# boatColorControlBiggerButtonV4.net
KiCad netlist of a schematic drawn in EAGLE
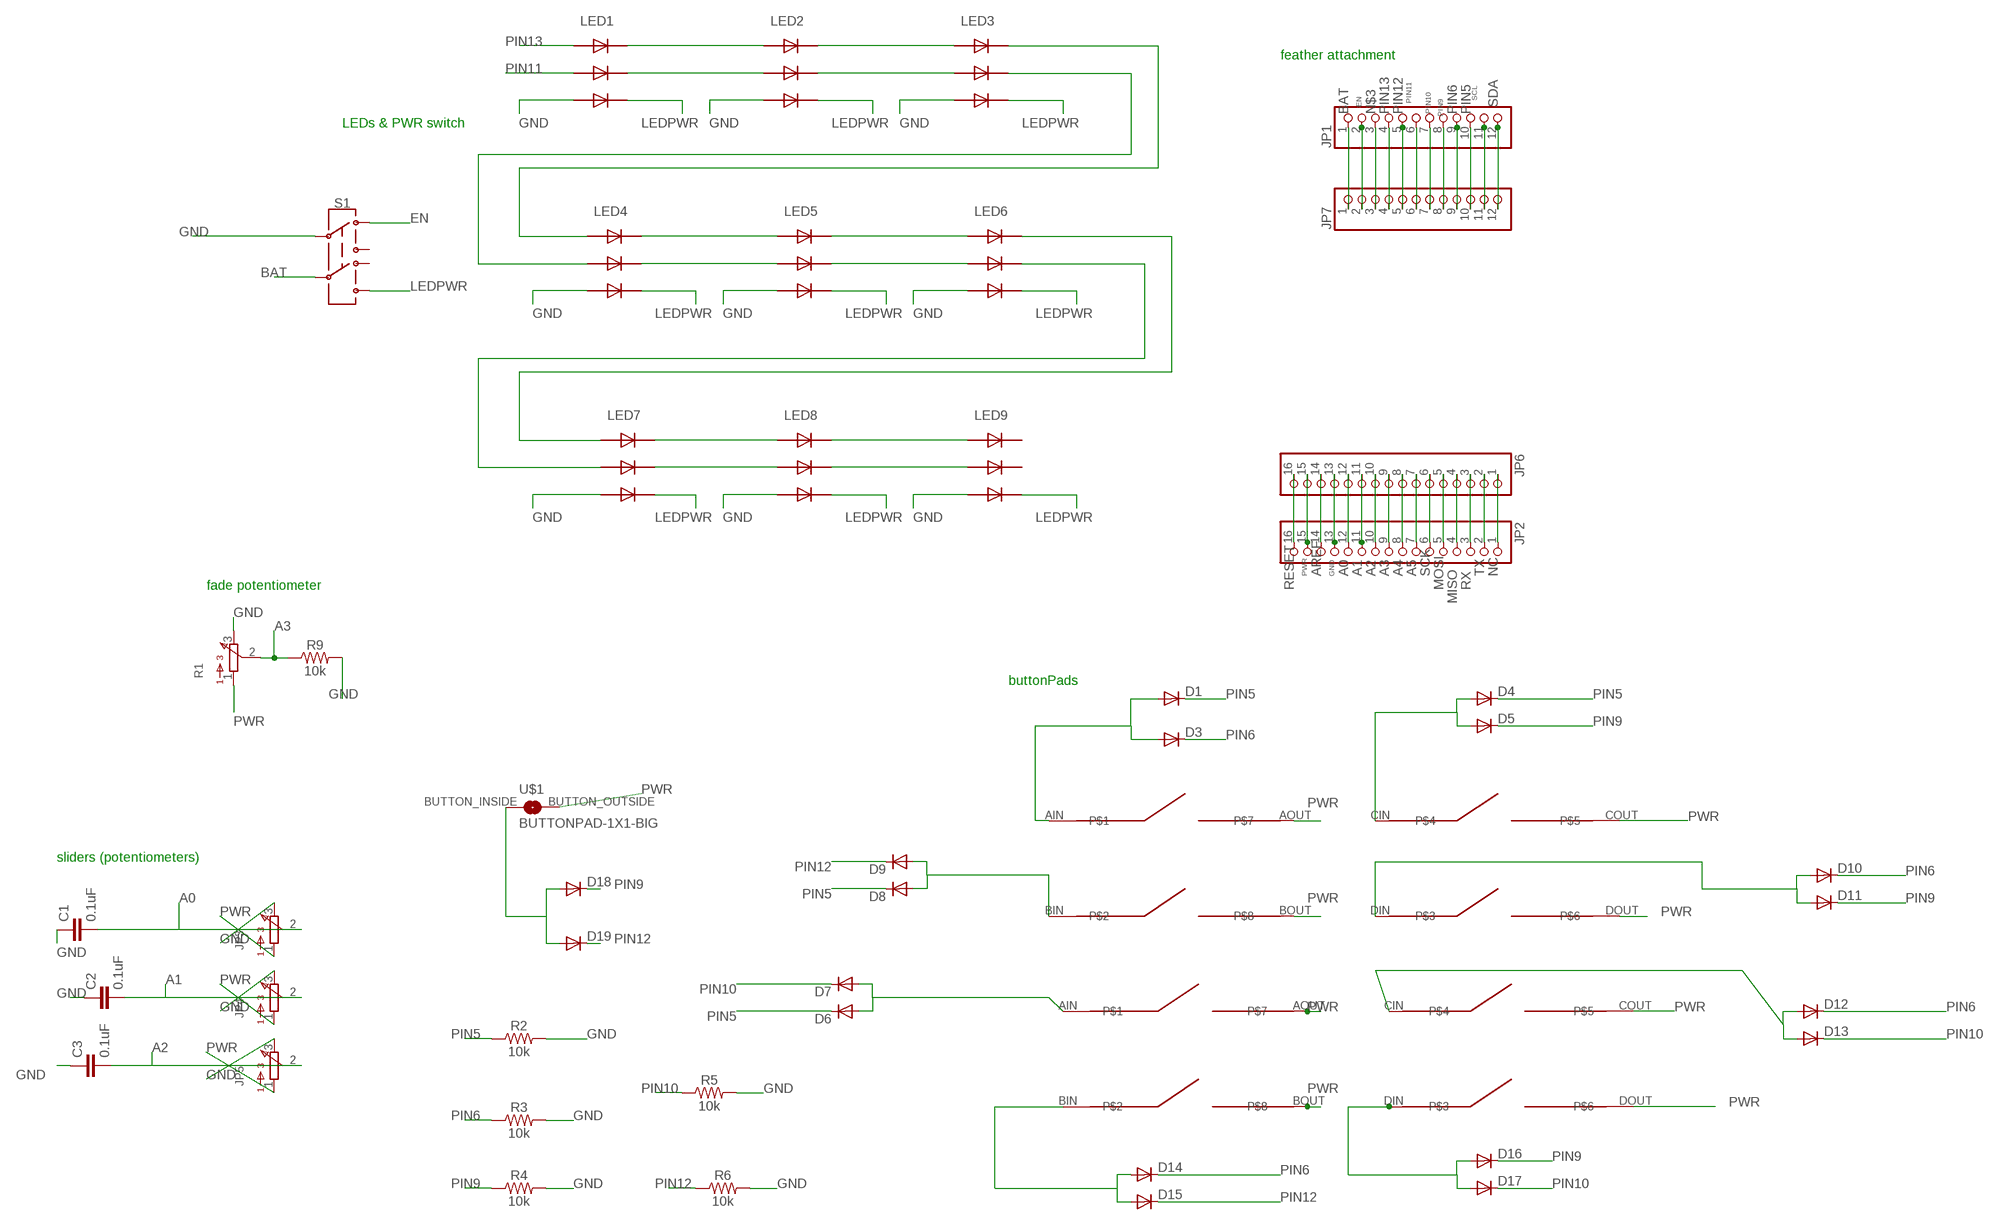
[diagram p0: schematic, sheet 1]

(export (version "E")
  (design (tool "Eeschema 10.0.6"))
  (components
    (comp (ref "C1")
      (value "0.1uF")
      (footprint "eagle-import:0603")
      (fields (field (name "PROD_ID") "CAP-08604"))
      (libsource (lib "eagle-import") (part "0.1UF-0603-25V-5%"))
    )
    (comp (ref "C2")
      (value "0.1uF")
      (footprint "eagle-import:0603")
      (libsource (lib "eagle-import") (part "0.1UF-0603-25V-5%"))
    )
    (comp (ref "C3")
      (value "0.1uF")
      (footprint "eagle-import:0603")
      (fields (field (name "PROD_ID") "CAP-08604"))
      (libsource (lib "eagle-import") (part "0.1UF-0603-25V-5%"))
    )
    (comp (ref "D1")
      (value "DIODESOD123")
      (footprint "eagle-import:SOD123")
      (libsource (lib "eagle-import") (part "DIODESOD123"))
    )
    (comp (ref "D3")
      (value "DIODESOD123")
      (footprint "eagle-import:SOD123")
      (libsource (lib "eagle-import") (part "DIODESOD123"))
    )
    (comp (ref "D4")
      (value "DIODESOD123")
      (footprint "eagle-import:SOD123")
      (libsource (lib "eagle-import") (part "DIODESOD123"))
    )
    (comp (ref "D5")
      (value "DIODESOD123")
      (footprint "eagle-import:SOD123")
      (libsource (lib "eagle-import") (part "DIODESOD123"))
    )
    (comp (ref "D6")
      (value "DIODESOD123")
      (footprint "eagle-import:SOD123")
      (libsource (lib "eagle-import") (part "DIODESOD123"))
    )
    (comp (ref "D7")
      (value "DIODESOD123")
      (footprint "eagle-import:SOD123")
      (libsource (lib "eagle-import") (part "DIODESOD123"))
    )
    (comp (ref "D8")
      (value "DIODESOD123")
      (footprint "eagle-import:SOD123")
      (libsource (lib "eagle-import") (part "DIODESOD123"))
    )
    (comp (ref "D9")
      (value "DIODESOD123")
      (footprint "eagle-import:SOD123")
      (libsource (lib "eagle-import") (part "DIODESOD123"))
    )
    (comp (ref "D10")
      (value "DIODESOD123")
      (footprint "eagle-import:SOD123")
      (libsource (lib "eagle-import") (part "DIODESOD123"))
    )
    (comp (ref "D11")
      (value "DIODESOD123")
      (footprint "eagle-import:SOD123")
      (libsource (lib "eagle-import") (part "DIODESOD123"))
    )
    (comp (ref "D12")
      (value "DIODESOD123")
      (footprint "eagle-import:SOD123")
      (libsource (lib "eagle-import") (part "DIODESOD123"))
    )
    (comp (ref "D13")
      (value "DIODESOD123")
      (footprint "eagle-import:SOD123")
      (libsource (lib "eagle-import") (part "DIODESOD123"))
    )
    (comp (ref "D14")
      (value "DIODESOD123")
      (footprint "eagle-import:SOD123")
      (libsource (lib "eagle-import") (part "DIODESOD123"))
    )
    (comp (ref "D15")
      (value "DIODESOD123")
      (footprint "eagle-import:SOD123")
      (libsource (lib "eagle-import") (part "DIODESOD123"))
    )
    (comp (ref "D16")
      (value "DIODESOD123")
      (footprint "eagle-import:SOD123")
      (libsource (lib "eagle-import") (part "DIODESOD123"))
    )
    (comp (ref "D17")
      (value "DIODESOD123")
      (footprint "eagle-import:SOD123")
      (libsource (lib "eagle-import") (part "DIODESOD123"))
    )
    (comp (ref "D18")
      (value "DIODESOD123")
      (footprint "eagle-import:SOD123")
      (libsource (lib "eagle-import") (part "DIODESOD123"))
    )
    (comp (ref "D19")
      (value "DIODESOD123")
      (footprint "eagle-import:SOD123")
      (libsource (lib "eagle-import") (part "DIODESOD123"))
    )
    (comp (ref "JP1")
      (value "PINHD-1X12")
      (footprint "eagle-import:1X12")
      (libsource (lib "eagle-import") (part "PINHD-1X12"))
    )
    (comp (ref "JP2")
      (value "PINHD-1X16")
      (footprint "eagle-import:1X16")
      (libsource (lib "eagle-import") (part "PINHD-1X16"))
    )
    (comp (ref "JP3")
      (value "BOURNESPOTENTIOMETER")
      (footprint "eagle-import:BOURNESPOTENTIOMETER")
      (libsource (lib "eagle-import") (part "BOURNESPOTENTIOMETER"))
    )
    (comp (ref "JP4")
      (value "BOURNESPOTENTIOMETER")
      (footprint "eagle-import:BOURNESPOTENTIOMETER")
      (libsource (lib "eagle-import") (part "BOURNESPOTENTIOMETER"))
    )
    (comp (ref "JP5")
      (value "BOURNESPOTENTIOMETER")
      (footprint "eagle-import:BOURNESPOTENTIOMETER")
      (libsource (lib "eagle-import") (part "BOURNESPOTENTIOMETER"))
    )
    (comp (ref "JP6")
      (value "PINHD-1X16")
      (footprint "eagle-import:1X16")
      (libsource (lib "eagle-import") (part "PINHD-1X16"))
    )
    (comp (ref "JP7")
      (value "PINHD-1X12")
      (footprint "eagle-import:1X12")
      (libsource (lib "eagle-import") (part "PINHD-1X12"))
    )
    (comp (ref "LED1")
      (value "RGBLED_DOTSTAR5050")
      (footprint "eagle-import:RGBLED5050_DOTSTAR")
      (libsource (lib "eagle-import") (part "RGBLED_DOTSTAR5050"))
    )
    (comp (ref "LED2")
      (value "RGBLED_DOTSTAR5050")
      (footprint "eagle-import:RGBLED5050_DOTSTAR")
      (libsource (lib "eagle-import") (part "RGBLED_DOTSTAR5050"))
    )
    (comp (ref "LED3")
      (value "RGBLED_DOTSTAR5050")
      (footprint "eagle-import:RGBLED5050_DOTSTAR")
      (libsource (lib "eagle-import") (part "RGBLED_DOTSTAR5050"))
    )
    (comp (ref "LED4")
      (value "RGBLED_DOTSTAR5050")
      (footprint "eagle-import:RGBLED5050_DOTSTAR")
      (libsource (lib "eagle-import") (part "RGBLED_DOTSTAR5050"))
    )
    (comp (ref "LED5")
      (value "RGBLED_DOTSTAR5050")
      (footprint "eagle-import:RGBLED5050_DOTSTAR")
      (libsource (lib "eagle-import") (part "RGBLED_DOTSTAR5050"))
    )
    (comp (ref "LED6")
      (value "RGBLED_DOTSTAR5050")
      (footprint "eagle-import:RGBLED5050_DOTSTAR")
      (libsource (lib "eagle-import") (part "RGBLED_DOTSTAR5050"))
    )
    (comp (ref "LED7")
      (value "RGBLED_DOTSTAR5050")
      (footprint "eagle-import:RGBLED5050_DOTSTAR")
      (libsource (lib "eagle-import") (part "RGBLED_DOTSTAR5050"))
    )
    (comp (ref "LED8")
      (value "RGBLED_DOTSTAR5050")
      (footprint "eagle-import:RGBLED5050_DOTSTAR")
      (libsource (lib "eagle-import") (part "RGBLED_DOTSTAR5050"))
    )
    (comp (ref "LED9")
      (value "RGBLED_DOTSTAR5050")
      (footprint "eagle-import:RGBLED5050_DOTSTAR")
      (libsource (lib "eagle-import") (part "RGBLED_DOTSTAR5050"))
    )
    (comp (ref "R1")
      (value "PTV_BOURNES_POT")
      (footprint "eagle-import:PVT_BOURNES_POT")
      (libsource (lib "eagle-import") (part "PTV_BOURNES_POT"))
    )
    (comp (ref "R2")
      (value "10k")
      (footprint "eagle-import:0603")
      (fields (field (name "PROD_ID") "RES-00824"))
      (libsource (lib "eagle-import") (part "10KOHM-0603-1/10W-1%"))
    )
    (comp (ref "R3")
      (value "10k")
      (footprint "eagle-import:0603")
      (fields (field (name "PROD_ID") "RES-00824"))
      (libsource (lib "eagle-import") (part "10KOHM-0603-1/10W-1%"))
    )
    (comp (ref "R4")
      (value "10k")
      (footprint "eagle-import:0603")
      (fields (field (name "PROD_ID") "RES-00824"))
      (libsource (lib "eagle-import") (part "10KOHM-0603-1/10W-1%"))
    )
    (comp (ref "R5")
      (value "10k")
      (footprint "eagle-import:0603")
      (fields (field (name "PROD_ID") "RES-00824"))
      (libsource (lib "eagle-import") (part "10KOHM-0603-1/10W-1%"))
    )
    (comp (ref "R6")
      (value "10k")
      (footprint "eagle-import:0603")
      (fields (field (name "PROD_ID") "RES-00824"))
      (libsource (lib "eagle-import") (part "10KOHM-0603-1/10W-1%"))
    )
    (comp (ref "R9")
      (value "10k")
      (footprint "eagle-import:0603")
      (libsource (lib "eagle-import") (part "10KOHM-0603-1/10W-1%"))
    )
    (comp (ref "S1")
      (value "SWITCH-DPDT-PTH-GPI-152-3013")
      (footprint "eagle-import:SWITCH_DPDT_CRFS-2202W")
      (libsource (lib "eagle-import") (part "SWITCH-DPDT-PTH-GPI-152-3013"))
    )
    (comp (ref "U$1")
      (value "BUTTONPAD-1X1-BIG")
      (footprint "eagle-import:BUTTONPAD-1X1")
      (libsource (lib "eagle-import") (part "BUTTONPAD-1X1-BIG"))
    )
    (comp (ref "U$9")
      (value "BUTTONPAD2X2")
      (footprint "eagle-import:BUTTONPAD-2X2")
      (libsource (lib "eagle-import") (part "BUTTONPAD2X2"))
    )
    (comp (ref "U$13")
      (value "BUTTONPAD2X2")
      (footprint "eagle-import:BUTTONPAD-2X2")
      (libsource (lib "eagle-import") (part "BUTTONPAD2X2"))
    )
  )
  (nets
    (net (code "1") (name "/A0") (class "Default")
      (node (ref "C1") (pin "2") (pinfunction "2_2") (pintype "passive"))
      (node (ref "JP2") (pin "12") (pinfunction "12_12") (pintype "passive"))
      (node (ref "JP3") (pin "2") (pinfunction "2_2") (pintype "passive"))
      (node (ref "JP6") (pin "12") (pinfunction "12_12") (pintype "passive"))
    )
    (net (code "2") (name "/A1") (class "Default")
      (node (ref "C2") (pin "2") (pinfunction "2_2") (pintype "passive"))
      (node (ref "JP2") (pin "11") (pinfunction "11_11") (pintype "passive"))
      (node (ref "JP4") (pin "2") (pinfunction "2_2") (pintype "passive"))
      (node (ref "JP6") (pin "11") (pinfunction "11_11") (pintype "passive"))
    )
    (net (code "3") (name "/A2") (class "Default")
      (node (ref "C3") (pin "2") (pinfunction "2_2") (pintype "passive"))
      (node (ref "JP2") (pin "10") (pinfunction "10_10") (pintype "passive"))
      (node (ref "JP5") (pin "2") (pinfunction "2_2") (pintype "passive"))
      (node (ref "JP6") (pin "10") (pinfunction "10_10") (pintype "passive"))
    )
    (net (code "4") (name "/A3") (class "Default")
      (node (ref "JP2") (pin "9") (pinfunction "9_9") (pintype "passive"))
      (node (ref "JP6") (pin "9") (pinfunction "9_9") (pintype "passive"))
      (node (ref "R1") (pin "2") (pinfunction "2_2") (pintype "passive"))
      (node (ref "R9") (pin "1") (pinfunction "1_1") (pintype "passive"))
    )
    (net (code "5") (name "/A4") (class "Default")
      (node (ref "JP2") (pin "8") (pinfunction "8_8") (pintype "passive"))
      (node (ref "JP6") (pin "8") (pinfunction "8_8") (pintype "passive"))
    )
    (net (code "6") (name "/A5") (class "Default")
      (node (ref "JP2") (pin "7") (pinfunction "7_7") (pintype "passive"))
      (node (ref "JP6") (pin "7") (pinfunction "7_7") (pintype "passive"))
    )
    (net (code "7") (name "/AREF") (class "Default")
      (node (ref "JP2") (pin "14") (pinfunction "14_14") (pintype "passive"))
      (node (ref "JP6") (pin "14") (pinfunction "14_14") (pintype "passive"))
    )
    (net (code "8") (name "/BAT") (class "Default")
      (node (ref "JP1") (pin "1") (pinfunction "1_1") (pintype "passive"))
      (node (ref "JP7") (pin "1") (pinfunction "1_1") (pintype "passive"))
      (node (ref "S1") (pin "C@2") (pinfunction "5_C@2") (pintype "bidirectional"))
    )
    (net (code "9") (name "/EN") (class "Default")
      (node (ref "JP1") (pin "2") (pinfunction "2_2") (pintype "passive"))
      (node (ref "JP7") (pin "2") (pinfunction "2_2") (pintype "passive"))
      (node (ref "S1") (pin "10") (pinfunction "1_10") (pintype "bidirectional"))
    )
    (net (code "10") (name "/GND") (class "Default")
      (node (ref "C1") (pin "1") (pinfunction "1_1") (pintype "passive"))
      (node (ref "C2") (pin "1") (pinfunction "1_1") (pintype "passive"))
      (node (ref "C3") (pin "1") (pinfunction "1_1") (pintype "passive"))
      (node (ref "JP2") (pin "13") (pinfunction "13_13") (pintype "passive"))
      (node (ref "JP3") (pin "3") (pinfunction "3_3") (pintype "passive"))
      (node (ref "JP4") (pin "3") (pinfunction "3_3") (pintype "passive"))
      (node (ref "JP5") (pin "3") (pinfunction "3_3") (pintype "passive"))
      (node (ref "JP6") (pin "13") (pinfunction "13_13") (pintype "passive"))
      (node (ref "LED1") (pin "GND") (pinfunction "GND_GND") (pintype "bidirectional"))
      (node (ref "LED2") (pin "GND") (pinfunction "GND_GND") (pintype "bidirectional"))
      (node (ref "LED3") (pin "GND") (pinfunction "GND_GND") (pintype "bidirectional"))
      (node (ref "LED4") (pin "GND") (pinfunction "GND_GND") (pintype "bidirectional"))
      (node (ref "LED5") (pin "GND") (pinfunction "GND_GND") (pintype "bidirectional"))
      (node (ref "LED6") (pin "GND") (pinfunction "GND_GND") (pintype "bidirectional"))
      (node (ref "LED7") (pin "GND") (pinfunction "GND_GND") (pintype "bidirectional"))
      (node (ref "LED8") (pin "GND") (pinfunction "GND_GND") (pintype "bidirectional"))
      (node (ref "LED9") (pin "GND") (pinfunction "GND_GND") (pintype "bidirectional"))
      (node (ref "R1") (pin "3") (pinfunction "3_3") (pintype "passive"))
      (node (ref "R2") (pin "2") (pinfunction "2_2") (pintype "passive"))
      (node (ref "R3") (pin "2") (pinfunction "2_2") (pintype "passive"))
      (node (ref "R4") (pin "2") (pinfunction "2_2") (pintype "passive"))
      (node (ref "R5") (pin "2") (pinfunction "2_2") (pintype "passive"))
      (node (ref "R6") (pin "2") (pinfunction "2_2") (pintype "passive"))
      (node (ref "R9") (pin "2") (pinfunction "2_2") (pintype "passive"))
      (node (ref "S1") (pin "C@1") (pinfunction "2_C@1") (pintype "bidirectional"))
    )
    (net (code "11") (name "/LEDPWR") (class "Default")
      (node (ref "LED1") (pin "VCC") (pinfunction "VCC_VCC") (pintype "bidirectional"))
      (node (ref "LED2") (pin "VCC") (pinfunction "VCC_VCC") (pintype "bidirectional"))
      (node (ref "LED3") (pin "VCC") (pinfunction "VCC_VCC") (pintype "bidirectional"))
      (node (ref "LED4") (pin "VCC") (pinfunction "VCC_VCC") (pintype "bidirectional"))
      (node (ref "LED5") (pin "VCC") (pinfunction "VCC_VCC") (pintype "bidirectional"))
      (node (ref "LED6") (pin "VCC") (pinfunction "VCC_VCC") (pintype "bidirectional"))
      (node (ref "LED7") (pin "VCC") (pinfunction "VCC_VCC") (pintype "bidirectional"))
      (node (ref "LED8") (pin "VCC") (pinfunction "VCC_VCC") (pintype "bidirectional"))
      (node (ref "LED9") (pin "VCC") (pinfunction "VCC_VCC") (pintype "bidirectional"))
      (node (ref "S1") (pin "21") (pinfunction "6_21") (pintype "bidirectional"))
    )
    (net (code "12") (name "/MISO") (class "Default")
      (node (ref "JP2") (pin "4") (pinfunction "4_4") (pintype "passive"))
      (node (ref "JP6") (pin "4") (pinfunction "4_4") (pintype "passive"))
    )
    (net (code "13") (name "/MOSI") (class "Default")
      (node (ref "JP2") (pin "5") (pinfunction "5_5") (pintype "passive"))
      (node (ref "JP6") (pin "5") (pinfunction "5_5") (pintype "passive"))
    )
    (net (code "14") (name "/N$3") (class "Default")
      (node (ref "JP1") (pin "3") (pinfunction "3_3") (pintype "passive"))
      (node (ref "JP7") (pin "3") (pinfunction "3_3") (pintype "passive"))
    )
    (net (code "15") (name "/NC") (class "Default")
      (node (ref "JP2") (pin "1") (pinfunction "1_1") (pintype "passive"))
      (node (ref "JP6") (pin "1") (pinfunction "1_1") (pintype "passive"))
    )
    (net (code "16") (name "/PIN5") (class "Default")
      (node (ref "D1") (pin "CATHODE") (pinfunction "C_CATHODE") (pintype "passive"))
      (node (ref "D4") (pin "CATHODE") (pinfunction "C_CATHODE") (pintype "passive"))
      (node (ref "D6") (pin "CATHODE") (pinfunction "C_CATHODE") (pintype "passive"))
      (node (ref "D8") (pin "CATHODE") (pinfunction "C_CATHODE") (pintype "passive"))
      (node (ref "JP1") (pin "10") (pinfunction "10_10") (pintype "passive"))
      (node (ref "JP7") (pin "10") (pinfunction "10_10") (pintype "passive"))
      (node (ref "R2") (pin "1") (pinfunction "1_1") (pintype "passive"))
    )
    (net (code "17") (name "/PIN6") (class "Default")
      (node (ref "D10") (pin "CATHODE") (pinfunction "C_CATHODE") (pintype "passive"))
      (node (ref "D12") (pin "CATHODE") (pinfunction "C_CATHODE") (pintype "passive"))
      (node (ref "D14") (pin "CATHODE") (pinfunction "C_CATHODE") (pintype "passive"))
      (node (ref "D3") (pin "CATHODE") (pinfunction "C_CATHODE") (pintype "passive"))
      (node (ref "JP1") (pin "9") (pinfunction "9_9") (pintype "passive"))
      (node (ref "JP7") (pin "9") (pinfunction "9_9") (pintype "passive"))
      (node (ref "R3") (pin "1") (pinfunction "1_1") (pintype "passive"))
    )
    (net (code "18") (name "/PIN9") (class "Default")
      (node (ref "D11") (pin "CATHODE") (pinfunction "C_CATHODE") (pintype "passive"))
      (node (ref "D16") (pin "CATHODE") (pinfunction "C_CATHODE") (pintype "passive"))
      (node (ref "D18") (pin "CATHODE") (pinfunction "C_CATHODE") (pintype "passive"))
      (node (ref "D5") (pin "CATHODE") (pinfunction "C_CATHODE") (pintype "passive"))
      (node (ref "JP1") (pin "8") (pinfunction "8_8") (pintype "passive"))
      (node (ref "JP7") (pin "8") (pinfunction "8_8") (pintype "passive"))
      (node (ref "R4") (pin "1") (pinfunction "1_1") (pintype "passive"))
    )
    (net (code "19") (name "/PIN10") (class "Default")
      (node (ref "D13") (pin "CATHODE") (pinfunction "C_CATHODE") (pintype "passive"))
      (node (ref "D17") (pin "CATHODE") (pinfunction "C_CATHODE") (pintype "passive"))
      (node (ref "D7") (pin "CATHODE") (pinfunction "C_CATHODE") (pintype "passive"))
      (node (ref "JP1") (pin "7") (pinfunction "7_7") (pintype "passive"))
      (node (ref "JP7") (pin "7") (pinfunction "7_7") (pintype "passive"))
      (node (ref "R5") (pin "1") (pinfunction "1_1") (pintype "passive"))
    )
    (net (code "20") (name "/PIN11") (class "Default")
      (node (ref "JP1") (pin "6") (pinfunction "6_6") (pintype "passive"))
      (node (ref "JP7") (pin "6") (pinfunction "6_6") (pintype "passive"))
      (node (ref "LED1") (pin "CLOCKIN") (pinfunction "CLOCKIN_CLOCKIN") (pintype "bidirectional"))
    )
    (net (code "21") (name "/PIN12") (class "Default")
      (node (ref "D15") (pin "CATHODE") (pinfunction "C_CATHODE") (pintype "passive"))
      (node (ref "D19") (pin "CATHODE") (pinfunction "C_CATHODE") (pintype "passive"))
      (node (ref "D9") (pin "CATHODE") (pinfunction "C_CATHODE") (pintype "passive"))
      (node (ref "JP1") (pin "5") (pinfunction "5_5") (pintype "passive"))
      (node (ref "JP7") (pin "5") (pinfunction "5_5") (pintype "passive"))
      (node (ref "R6") (pin "1") (pinfunction "1_1") (pintype "passive"))
    )
    (net (code "22") (name "/PIN13") (class "Default")
      (node (ref "JP1") (pin "4") (pinfunction "4_4") (pintype "passive"))
      (node (ref "JP7") (pin "4") (pinfunction "4_4") (pintype "passive"))
      (node (ref "LED1") (pin "DATAIN") (pinfunction "DATAIN_DATAIN") (pintype "bidirectional"))
    )
    (net (code "23") (name "/PWR") (class "Default")
      (node (ref "JP2") (pin "15") (pinfunction "15_15") (pintype "passive"))
      (node (ref "JP3") (pin "1") (pinfunction "1_1") (pintype "passive"))
      (node (ref "JP4") (pin "1") (pinfunction "1_1") (pintype "passive"))
      (node (ref "JP5") (pin "1") (pinfunction "1_1") (pintype "passive"))
      (node (ref "JP6") (pin "15") (pinfunction "15_15") (pintype "passive"))
      (node (ref "R1") (pin "1") (pinfunction "1_1") (pintype "passive"))
      (node (ref "U$1") (pin "BUTTON_OUTSIDE") (pinfunction "BUTTONOUTSIDE_BUTTON_OUTSIDE") (pintype "passive"))
      (node (ref "U$13") (pin "AOUT") (pinfunction "P$7_AOUT") (pintype "bidirectional"))
      (node (ref "U$13") (pin "BOUT") (pinfunction "P$8_BOUT") (pintype "bidirectional"))
      (node (ref "U$13") (pin "COUT") (pinfunction "P$5_COUT") (pintype "bidirectional"))
      (node (ref "U$13") (pin "DOUT") (pinfunction "P$6_DOUT") (pintype "bidirectional"))
      (node (ref "U$9") (pin "AOUT") (pinfunction "P$7_AOUT") (pintype "bidirectional"))
      (node (ref "U$9") (pin "BOUT") (pinfunction "P$8_BOUT") (pintype "bidirectional"))
      (node (ref "U$9") (pin "COUT") (pinfunction "P$5_COUT") (pintype "bidirectional"))
      (node (ref "U$9") (pin "DOUT") (pinfunction "P$6_DOUT") (pintype "bidirectional"))
    )
    (net (code "24") (name "/RESET") (class "Default")
      (node (ref "JP2") (pin "16") (pinfunction "16_16") (pintype "passive"))
      (node (ref "JP6") (pin "16") (pinfunction "16_16") (pintype "passive"))
    )
    (net (code "25") (name "/RX") (class "Default")
      (node (ref "JP2") (pin "3") (pinfunction "3_3") (pintype "passive"))
      (node (ref "JP6") (pin "3") (pinfunction "3_3") (pintype "passive"))
    )
    (net (code "26") (name "/SCK") (class "Default")
      (node (ref "JP2") (pin "6") (pinfunction "6_6") (pintype "passive"))
      (node (ref "JP6") (pin "6") (pinfunction "6_6") (pintype "passive"))
    )
    (net (code "27") (name "/SCL") (class "Default")
      (node (ref "JP1") (pin "11") (pinfunction "11_11") (pintype "passive"))
      (node (ref "JP7") (pin "11") (pinfunction "11_11") (pintype "passive"))
    )
    (net (code "28") (name "/SDA") (class "Default")
      (node (ref "JP1") (pin "12") (pinfunction "12_12") (pintype "passive"))
      (node (ref "JP7") (pin "12") (pinfunction "12_12") (pintype "passive"))
    )
    (net (code "29") (name "/TX") (class "Default")
      (node (ref "JP2") (pin "2") (pinfunction "2_2") (pintype "passive"))
      (node (ref "JP6") (pin "2") (pinfunction "2_2") (pintype "passive"))
    )
    (net (code "30") (name "Net-(D1-A)") (class "Default")
      (node (ref "D1") (pin "ANODE") (pinfunction "A_ANODE") (pintype "passive"))
      (node (ref "D3") (pin "ANODE") (pinfunction "A_ANODE") (pintype "passive"))
      (node (ref "U$9") (pin "AIN") (pinfunction "P$1_AIN") (pintype "bidirectional"))
    )
    (net (code "31") (name "Net-(D4-A)") (class "Default")
      (node (ref "D4") (pin "ANODE") (pinfunction "A_ANODE") (pintype "passive"))
      (node (ref "D5") (pin "ANODE") (pinfunction "A_ANODE") (pintype "passive"))
      (node (ref "U$9") (pin "CIN") (pinfunction "P$4_CIN") (pintype "bidirectional"))
    )
    (net (code "32") (name "Net-(D6-A)") (class "Default")
      (node (ref "D6") (pin "ANODE") (pinfunction "A_ANODE") (pintype "passive"))
      (node (ref "D7") (pin "ANODE") (pinfunction "A_ANODE") (pintype "passive"))
      (node (ref "U$13") (pin "AIN") (pinfunction "P$1_AIN") (pintype "bidirectional"))
    )
    (net (code "33") (name "Net-(D8-A)") (class "Default")
      (node (ref "D8") (pin "ANODE") (pinfunction "A_ANODE") (pintype "passive"))
      (node (ref "D9") (pin "ANODE") (pinfunction "A_ANODE") (pintype "passive"))
      (node (ref "U$9") (pin "BIN") (pinfunction "P$2_BIN") (pintype "bidirectional"))
    )
    (net (code "34") (name "Net-(D10-A)") (class "Default")
      (node (ref "D10") (pin "ANODE") (pinfunction "A_ANODE") (pintype "passive"))
      (node (ref "D11") (pin "ANODE") (pinfunction "A_ANODE") (pintype "passive"))
      (node (ref "U$9") (pin "DIN") (pinfunction "P$3_DIN") (pintype "bidirectional"))
    )
    (net (code "35") (name "Net-(D12-A)") (class "Default")
      (node (ref "D12") (pin "ANODE") (pinfunction "A_ANODE") (pintype "passive"))
      (node (ref "D13") (pin "ANODE") (pinfunction "A_ANODE") (pintype "passive"))
      (node (ref "U$13") (pin "CIN") (pinfunction "P$4_CIN") (pintype "bidirectional"))
    )
    (net (code "36") (name "Net-(D14-A)") (class "Default")
      (node (ref "D14") (pin "ANODE") (pinfunction "A_ANODE") (pintype "passive"))
      (node (ref "D15") (pin "ANODE") (pinfunction "A_ANODE") (pintype "passive"))
      (node (ref "U$13") (pin "BIN") (pinfunction "P$2_BIN") (pintype "bidirectional"))
    )
    (net (code "37") (name "Net-(D16-A)") (class "Default")
      (node (ref "D16") (pin "ANODE") (pinfunction "A_ANODE") (pintype "passive"))
      (node (ref "D17") (pin "ANODE") (pinfunction "A_ANODE") (pintype "passive"))
      (node (ref "U$13") (pin "DIN") (pinfunction "P$3_DIN") (pintype "bidirectional"))
    )
    (net (code "38") (name "Net-(D18-A)") (class "Default")
      (node (ref "D18") (pin "ANODE") (pinfunction "A_ANODE") (pintype "passive"))
      (node (ref "D19") (pin "ANODE") (pinfunction "A_ANODE") (pintype "passive"))
      (node (ref "U$1") (pin "BUTTON_INSIDE") (pinfunction "BUTTONINSIDE_BUTTON_INSIDE") (pintype "passive"))
    )
    (net (code "39") (name "Net-(LED1-PadCLOCKOUT)") (class "Default")
      (node (ref "LED1") (pin "CLOCKOUT") (pinfunction "CLOCKOUT_CLOCKOUT") (pintype "bidirectional"))
      (node (ref "LED2") (pin "CLOCKIN") (pinfunction "CLOCKIN_CLOCKIN") (pintype "bidirectional"))
    )
    (net (code "40") (name "Net-(LED1-PadDATAOUT)") (class "Default")
      (node (ref "LED1") (pin "DATAOUT") (pinfunction "DATAOUT_DATAOUT") (pintype "bidirectional"))
      (node (ref "LED2") (pin "DATAIN") (pinfunction "DATAIN_DATAIN") (pintype "bidirectional"))
    )
    (net (code "41") (name "Net-(LED2-PadCLOCKOUT)") (class "Default")
      (node (ref "LED2") (pin "CLOCKOUT") (pinfunction "CLOCKOUT_CLOCKOUT") (pintype "bidirectional"))
      (node (ref "LED3") (pin "CLOCKIN") (pinfunction "CLOCKIN_CLOCKIN") (pintype "bidirectional"))
    )
    (net (code "42") (name "Net-(LED2-PadDATAOUT)") (class "Default")
      (node (ref "LED2") (pin "DATAOUT") (pinfunction "DATAOUT_DATAOUT") (pintype "bidirectional"))
      (node (ref "LED3") (pin "DATAIN") (pinfunction "DATAIN_DATAIN") (pintype "bidirectional"))
    )
    (net (code "43") (name "Net-(LED3-PadCLOCKOUT)") (class "Default")
      (node (ref "LED3") (pin "CLOCKOUT") (pinfunction "CLOCKOUT_CLOCKOUT") (pintype "bidirectional"))
      (node (ref "LED4") (pin "CLOCKIN") (pinfunction "CLOCKIN_CLOCKIN") (pintype "bidirectional"))
    )
    (net (code "44") (name "Net-(LED3-PadDATAOUT)") (class "Default")
      (node (ref "LED3") (pin "DATAOUT") (pinfunction "DATAOUT_DATAOUT") (pintype "bidirectional"))
      (node (ref "LED4") (pin "DATAIN") (pinfunction "DATAIN_DATAIN") (pintype "bidirectional"))
    )
    (net (code "45") (name "Net-(LED4-PadCLOCKOUT)") (class "Default")
      (node (ref "LED4") (pin "CLOCKOUT") (pinfunction "CLOCKOUT_CLOCKOUT") (pintype "bidirectional"))
      (node (ref "LED5") (pin "CLOCKIN") (pinfunction "CLOCKIN_CLOCKIN") (pintype "bidirectional"))
    )
    (net (code "46") (name "Net-(LED4-PadDATAOUT)") (class "Default")
      (node (ref "LED4") (pin "DATAOUT") (pinfunction "DATAOUT_DATAOUT") (pintype "bidirectional"))
      (node (ref "LED5") (pin "DATAIN") (pinfunction "DATAIN_DATAIN") (pintype "bidirectional"))
    )
    (net (code "47") (name "Net-(LED5-PadCLOCKOUT)") (class "Default")
      (node (ref "LED5") (pin "CLOCKOUT") (pinfunction "CLOCKOUT_CLOCKOUT") (pintype "bidirectional"))
      (node (ref "LED6") (pin "CLOCKIN") (pinfunction "CLOCKIN_CLOCKIN") (pintype "bidirectional"))
    )
    (net (code "48") (name "Net-(LED5-PadDATAOUT)") (class "Default")
      (node (ref "LED5") (pin "DATAOUT") (pinfunction "DATAOUT_DATAOUT") (pintype "bidirectional"))
      (node (ref "LED6") (pin "DATAIN") (pinfunction "DATAIN_DATAIN") (pintype "bidirectional"))
    )
    (net (code "49") (name "Net-(LED6-PadCLOCKOUT)") (class "Default")
      (node (ref "LED6") (pin "CLOCKOUT") (pinfunction "CLOCKOUT_CLOCKOUT") (pintype "bidirectional"))
      (node (ref "LED7") (pin "CLOCKIN") (pinfunction "CLOCKIN_CLOCKIN") (pintype "bidirectional"))
    )
    (net (code "50") (name "Net-(LED6-PadDATAOUT)") (class "Default")
      (node (ref "LED6") (pin "DATAOUT") (pinfunction "DATAOUT_DATAOUT") (pintype "bidirectional"))
      (node (ref "LED7") (pin "DATAIN") (pinfunction "DATAIN_DATAIN") (pintype "bidirectional"))
    )
    (net (code "51") (name "Net-(LED7-PadCLOCKOUT)") (class "Default")
      (node (ref "LED7") (pin "CLOCKOUT") (pinfunction "CLOCKOUT_CLOCKOUT") (pintype "bidirectional"))
      (node (ref "LED8") (pin "CLOCKIN") (pinfunction "CLOCKIN_CLOCKIN") (pintype "bidirectional"))
    )
    (net (code "52") (name "Net-(LED7-PadDATAOUT)") (class "Default")
      (node (ref "LED7") (pin "DATAOUT") (pinfunction "DATAOUT_DATAOUT") (pintype "bidirectional"))
      (node (ref "LED8") (pin "DATAIN") (pinfunction "DATAIN_DATAIN") (pintype "bidirectional"))
    )
    (net (code "53") (name "Net-(LED8-PadCLOCKOUT)") (class "Default")
      (node (ref "LED8") (pin "CLOCKOUT") (pinfunction "CLOCKOUT_CLOCKOUT") (pintype "bidirectional"))
      (node (ref "LED9") (pin "CLOCKIN") (pinfunction "CLOCKIN_CLOCKIN") (pintype "bidirectional"))
    )
    (net (code "54") (name "Net-(LED8-PadDATAOUT)") (class "Default")
      (node (ref "LED8") (pin "DATAOUT") (pinfunction "DATAOUT_DATAOUT") (pintype "bidirectional"))
      (node (ref "LED9") (pin "DATAIN") (pinfunction "DATAIN_DATAIN") (pintype "bidirectional"))
    )
    (net (code "55") (name "unconnected-(LED9-PadCLOCKOUT)") (class "Default")
      (node (ref "LED9") (pin "CLOCKOUT") (pinfunction "CLOCKOUT_CLOCKOUT") (pintype "bidirectional"))
    )
    (net (code "56") (name "unconnected-(LED9-PadDATAOUT)") (class "Default")
      (node (ref "LED9") (pin "DATAOUT") (pinfunction "DATAOUT_DATAOUT") (pintype "bidirectional"))
    )
    (net (code "57") (name "unconnected-(S1-3-Pad20)") (class "Default")
      (node (ref "S1") (pin "20") (pinfunction "3_20") (pintype "bidirectional"))
    )
    (net (code "58") (name "unconnected-(S1-4-Pad11)") (class "Default")
      (node (ref "S1") (pin "11") (pinfunction "4_11") (pintype "bidirectional"))
    )
  )
)
